# controlador_lineal.net
KiCad netlist of a schematic drawn in Altium Designer
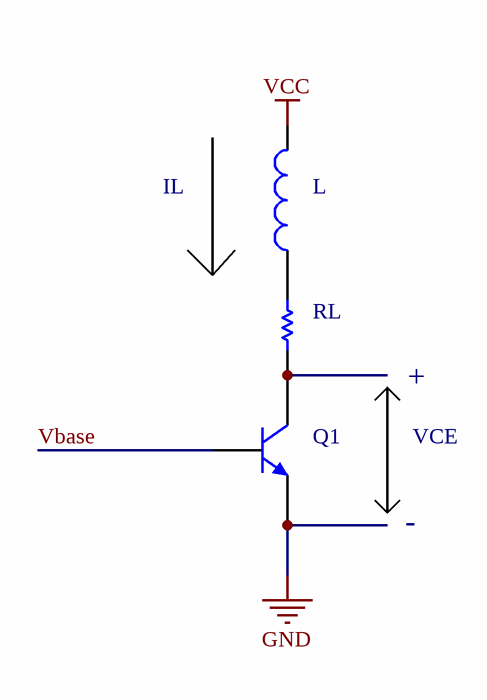
[diagram p0: controlador_lineal.SchDoc]

(export (version "E")
  (design (tool "Eeschema 10.0.6"))
  (components
    (comp (ref "L")
      (value "Inductor")
      (footprint "0402-A")
      (fields (field (name "PUBLISHER") "Altium Limited"))
      (libsource (lib "Miscellaneous Devices") (part "Inductor"))
    )
    (comp (ref "Q1")
      (value "2N3904")
      (footprint "TO-92A")
      (description "NPN General Purpose Amplifier")
      (fields (field (name "PUBLISHER") "Altium Limited"))
      (libsource (lib "Miscellaneous Devices") (part "2N3904"))
    )
    (comp (ref "RL")
      (value "Res1")
      (footprint "AXIAL-0.3")
      (description "Resistor")
      (fields (field (name "PUBLISHER") "Altium Limited"))
      (libsource (lib "Miscellaneous Devices") (part "Res1"))
    )
  )
  (nets
    (net (code "1") (name "/Vbase") (class "Default")
      (node (ref "Q1") (pin "2") (pinfunction "B_2") (pintype "passive"))
    )
    (net (code "2") (name "GND") (class "Default")
      (node (ref "Q1") (pin "1") (pinfunction "E_1") (pintype "passive"))
    )
    (net (code "3") (name "Net-(L-Pad1)") (class "Default")
      (node (ref "L") (pin "1") (pinfunction "1_1") (pintype "passive"))
      (node (ref "RL") (pin "2") (pinfunction "2_2") (pintype "passive"))
    )
    (net (code "4") (name "Net-(Q1-C)") (class "Default")
      (node (ref "Q1") (pin "3") (pinfunction "C_3") (pintype "passive"))
      (node (ref "RL") (pin "1") (pinfunction "1_1") (pintype "passive"))
    )
    (net (code "5") (name "VCC") (class "Default")
      (node (ref "L") (pin "2") (pinfunction "2_2") (pintype "passive"))
    )
  )
)
